# WS2812-Ring.net
KiCad netlist of a schematic drawn in EAGLE
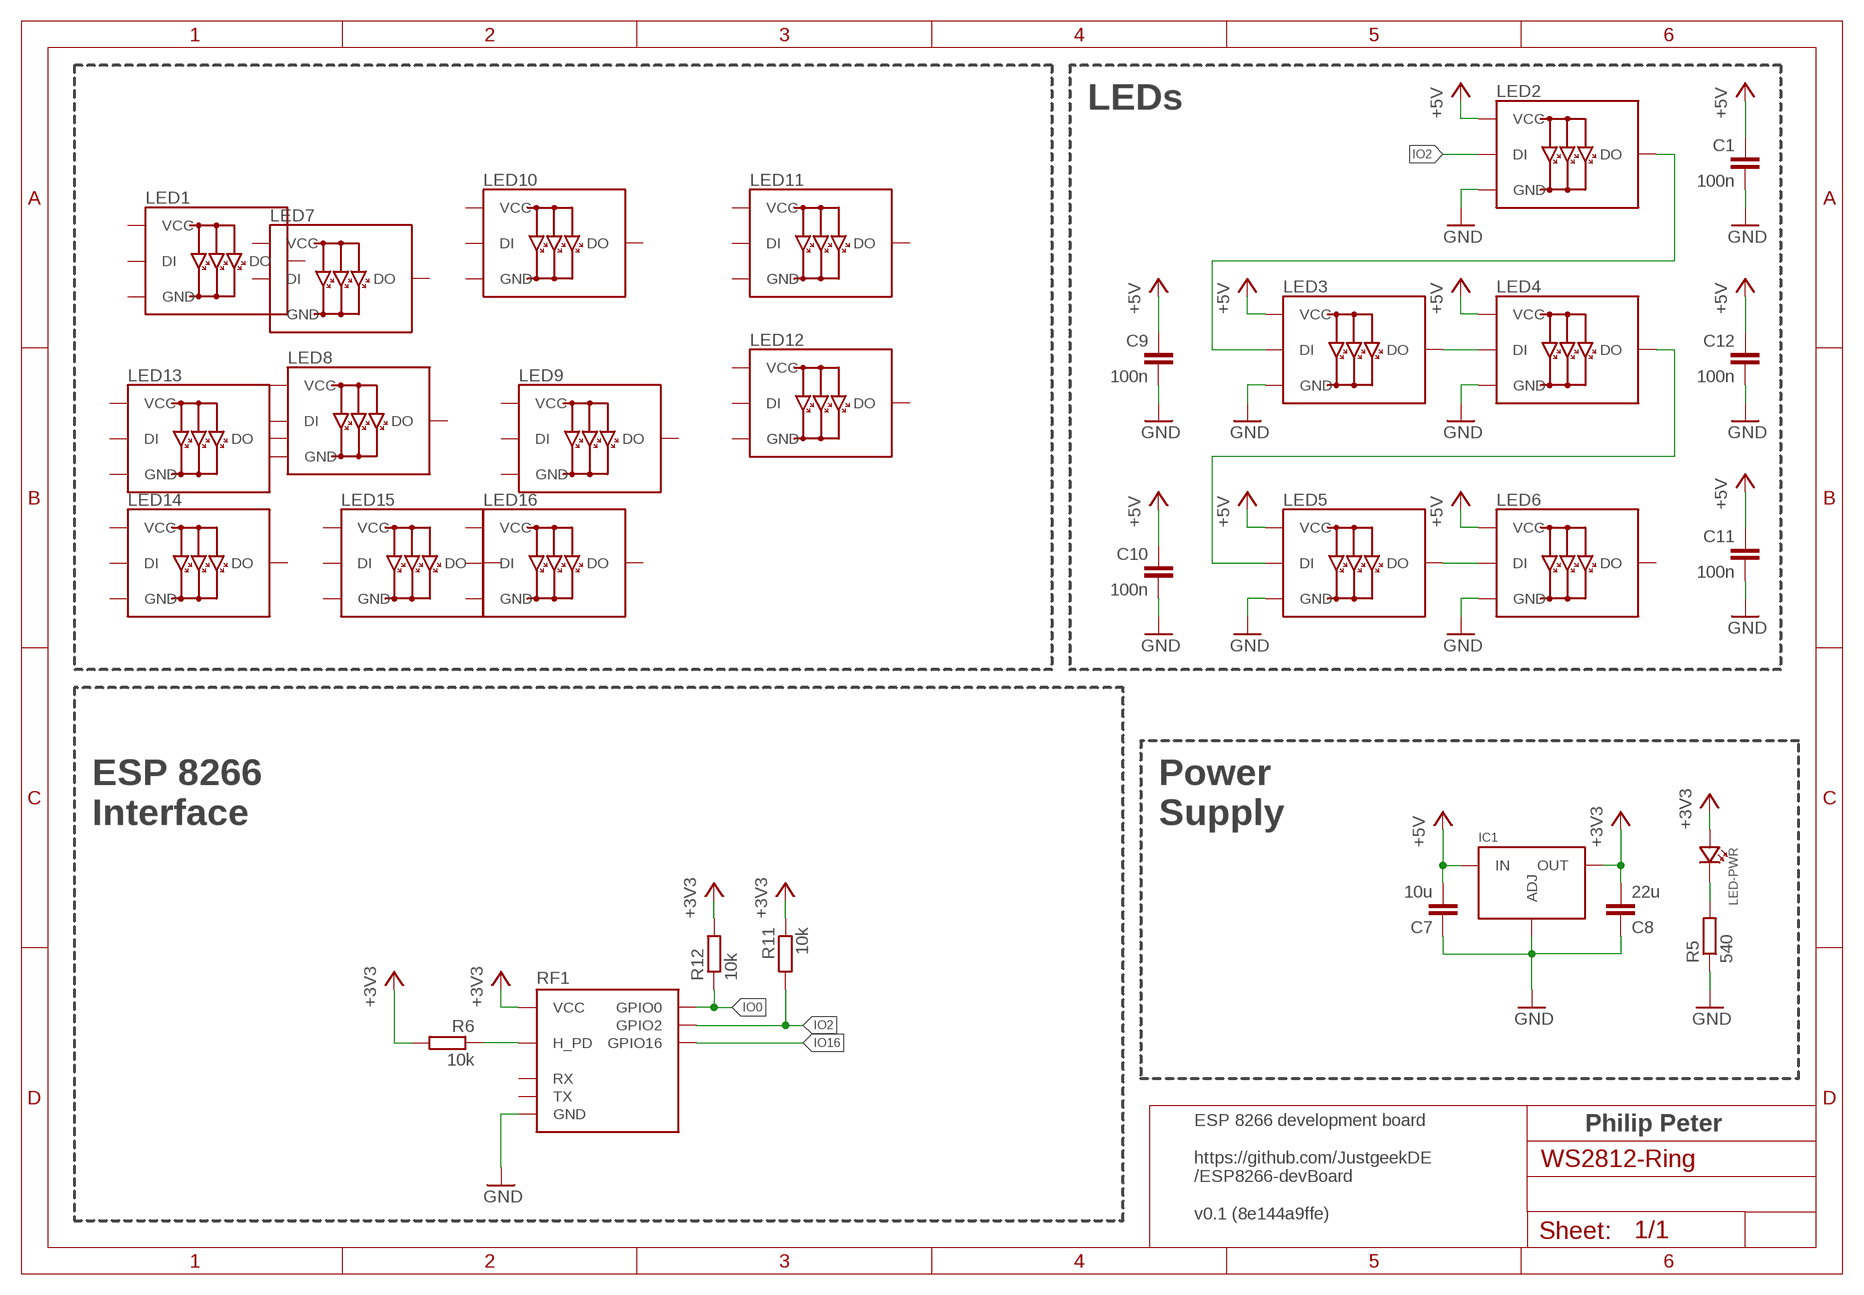
[diagram p0: schematic, sheet 1]

(export (version "E")
  (design (tool "Eeschema 10.0.6"))
  (components
    (comp (ref "C1")
      (value "100n")
      (footprint "eagle-import:C0805")
      (libsource (lib "eagle-import") (part "C-EUC0805"))
    )
    (comp (ref "C7")
      (value "10u")
      (footprint "eagle-import:C0805")
      (libsource (lib "eagle-import") (part "C-EUC0805"))
    )
    (comp (ref "C8")
      (value "22u")
      (footprint "eagle-import:C0805")
      (libsource (lib "eagle-import") (part "C-EUC0805"))
    )
    (comp (ref "C9")
      (value "100n")
      (footprint "eagle-import:C0805")
      (libsource (lib "eagle-import") (part "C-EUC0805"))
    )
    (comp (ref "C10")
      (value "100n")
      (footprint "eagle-import:C0805")
      (libsource (lib "eagle-import") (part "C-EUC0805"))
    )
    (comp (ref "C11")
      (value "100n")
      (footprint "eagle-import:C0805")
      (libsource (lib "eagle-import") (part "C-EUC0805"))
    )
    (comp (ref "C12")
      (value "100n")
      (footprint "eagle-import:C0805")
      (libsource (lib "eagle-import") (part "C-EUC0805"))
    )
    (comp (ref "IC1")
      (value "REGULATOR-LM317-SOT223")
      (footprint "eagle-import:SOT223")
      (libsource (lib "eagle-import") (part "REGULATOR-LM317-SOT223"))
    )
    (comp (ref "LED-PWR")
      (value "LED0805")
      (footprint "eagle-import:CHIPLED_0805")
      (libsource (lib "eagle-import") (part "LED0805"))
    )
    (comp (ref "LED1")
      (value "WS2812B")
      (footprint "eagle-import:CHIP-5050-4_PIN")
      (libsource (lib "eagle-import") (part "WS2812B"))
    )
    (comp (ref "LED2")
      (value "WS2812B")
      (footprint "eagle-import:CHIP-5050-4_PIN")
      (libsource (lib "eagle-import") (part "WS2812B"))
    )
    (comp (ref "LED3")
      (value "WS2812B")
      (footprint "eagle-import:CHIP-5050-4_PIN")
      (libsource (lib "eagle-import") (part "WS2812B"))
    )
    (comp (ref "LED4")
      (value "WS2812B")
      (footprint "eagle-import:CHIP-5050-4_PIN")
      (libsource (lib "eagle-import") (part "WS2812B"))
    )
    (comp (ref "LED5")
      (value "WS2812B")
      (footprint "eagle-import:CHIP-5050-4_PIN")
      (libsource (lib "eagle-import") (part "WS2812B"))
    )
    (comp (ref "LED6")
      (value "WS2812B")
      (footprint "eagle-import:CHIP-5050-4_PIN")
      (libsource (lib "eagle-import") (part "WS2812B"))
    )
    (comp (ref "LED7")
      (value "WS2812B")
      (footprint "eagle-import:CHIP-5050-4_PIN")
      (libsource (lib "eagle-import") (part "WS2812B"))
    )
    (comp (ref "LED8")
      (value "WS2812B")
      (footprint "eagle-import:CHIP-5050-4_PIN")
      (libsource (lib "eagle-import") (part "WS2812B"))
    )
    (comp (ref "LED9")
      (value "WS2812B")
      (footprint "eagle-import:CHIP-5050-4_PIN")
      (libsource (lib "eagle-import") (part "WS2812B"))
    )
    (comp (ref "LED10")
      (value "WS2812B")
      (footprint "eagle-import:CHIP-5050-4_PIN")
      (libsource (lib "eagle-import") (part "WS2812B"))
    )
    (comp (ref "LED11")
      (value "WS2812B")
      (footprint "eagle-import:CHIP-5050-4_PIN")
      (libsource (lib "eagle-import") (part "WS2812B"))
    )
    (comp (ref "LED12")
      (value "WS2812B")
      (footprint "eagle-import:CHIP-5050-4_PIN")
      (libsource (lib "eagle-import") (part "WS2812B"))
    )
    (comp (ref "LED13")
      (value "WS2812B")
      (footprint "eagle-import:CHIP-5050-4_PIN")
      (libsource (lib "eagle-import") (part "WS2812B"))
    )
    (comp (ref "LED14")
      (value "WS2812B")
      (footprint "eagle-import:CHIP-5050-4_PIN")
      (libsource (lib "eagle-import") (part "WS2812B"))
    )
    (comp (ref "LED15")
      (value "WS2812B")
      (footprint "eagle-import:CHIP-5050-4_PIN")
      (libsource (lib "eagle-import") (part "WS2812B"))
    )
    (comp (ref "LED16")
      (value "WS2812B")
      (footprint "eagle-import:CHIP-5050-4_PIN")
      (libsource (lib "eagle-import") (part "WS2812B"))
    )
    (comp (ref "R5")
      (value "540")
      (footprint "eagle-import:R0805")
      (libsource (lib "eagle-import") (part "R-EU_R0805"))
    )
    (comp (ref "R6")
      (value "10k")
      (footprint "eagle-import:R0805")
      (libsource (lib "eagle-import") (part "R-EU_R0805"))
    )
    (comp (ref "R11")
      (value "10k")
      (footprint "eagle-import:R0805")
      (libsource (lib "eagle-import") (part "R-EU_R0805"))
    )
    (comp (ref "R12")
      (value "10k")
      (footprint "eagle-import:R0805")
      (libsource (lib "eagle-import") (part "R-EU_R0805"))
    )
    (comp (ref "RF1")
      (value "ESP2866-ESP-01THT")
      (footprint "eagle-import:ESP8266-ESP-01")
      (libsource (lib "eagle-import") (part "ESP2866-ESP-01THT"))
    )
  )
  (nets
    (net (code "1") (name "+3V3") (class "Default")
      (node (ref "C8") (pin "2") (pinfunction "2_2") (pintype "passive"))
      (node (ref "IC1") (pin "2") (pinfunction "OUT_2") (pintype "bidirectional"))
      (node (ref "IC1") (pin "4") (pinfunction "OUT_4") (pintype "bidirectional"))
      (node (ref "LED-PWR") (pin "A") (pinfunction "A_A") (pintype "bidirectional"))
      (node (ref "R11") (pin "1") (pinfunction "1_1") (pintype "passive"))
      (node (ref "R12") (pin "2") (pinfunction "2_2") (pintype "passive"))
      (node (ref "R6") (pin "2") (pinfunction "2_2") (pintype "passive"))
      (node (ref "RF1") (pin "VCC") (pinfunction "VCC_VCC") (pintype "bidirectional"))
    )
    (net (code "2") (name "+5V") (class "Default")
      (node (ref "C1") (pin "1") (pinfunction "1_1") (pintype "passive"))
      (node (ref "C10") (pin "1") (pinfunction "1_1") (pintype "passive"))
      (node (ref "C11") (pin "1") (pinfunction "1_1") (pintype "passive"))
      (node (ref "C12") (pin "1") (pinfunction "1_1") (pintype "passive"))
      (node (ref "C7") (pin "2") (pinfunction "2_2") (pintype "passive"))
      (node (ref "C9") (pin "1") (pinfunction "1_1") (pintype "passive"))
      (node (ref "IC1") (pin "3") (pinfunction "IN_3") (pintype "bidirectional"))
      (node (ref "LED2") (pin "P$1") (pinfunction "VCC_P$1") (pintype "bidirectional"))
      (node (ref "LED3") (pin "P$1") (pinfunction "VCC_P$1") (pintype "bidirectional"))
      (node (ref "LED4") (pin "P$1") (pinfunction "VCC_P$1") (pintype "bidirectional"))
      (node (ref "LED5") (pin "P$1") (pinfunction "VCC_P$1") (pintype "bidirectional"))
      (node (ref "LED6") (pin "P$1") (pinfunction "VCC_P$1") (pintype "bidirectional"))
    )
    (net (code "3") (name "GND") (class "Default")
      (node (ref "C1") (pin "2") (pinfunction "2_2") (pintype "passive"))
      (node (ref "C10") (pin "2") (pinfunction "2_2") (pintype "passive"))
      (node (ref "C11") (pin "2") (pinfunction "2_2") (pintype "passive"))
      (node (ref "C12") (pin "2") (pinfunction "2_2") (pintype "passive"))
      (node (ref "C7") (pin "1") (pinfunction "1_1") (pintype "passive"))
      (node (ref "C8") (pin "1") (pinfunction "1_1") (pintype "passive"))
      (node (ref "C9") (pin "2") (pinfunction "2_2") (pintype "passive"))
      (node (ref "IC1") (pin "1") (pinfunction "ADJ_1") (pintype "bidirectional"))
      (node (ref "LED2") (pin "P$3") (pinfunction "GND_P$3") (pintype "bidirectional"))
      (node (ref "LED3") (pin "P$3") (pinfunction "GND_P$3") (pintype "bidirectional"))
      (node (ref "LED4") (pin "P$3") (pinfunction "GND_P$3") (pintype "bidirectional"))
      (node (ref "LED5") (pin "P$3") (pinfunction "GND_P$3") (pintype "bidirectional"))
      (node (ref "LED6") (pin "P$3") (pinfunction "GND_P$3") (pintype "bidirectional"))
      (node (ref "R5") (pin "1") (pinfunction "1_1") (pintype "passive"))
      (node (ref "RF1") (pin "GND") (pinfunction "GND_GND") (pintype "bidirectional"))
    )
    (net (code "4") (name "IO0") (class "Default")
      (node (ref "R12") (pin "1") (pinfunction "1_1") (pintype "passive"))
      (node (ref "RF1") (pin "GPIO0") (pinfunction "GPIO0_GPIO0") (pintype "bidirectional"))
    )
    (net (code "5") (name "IO2") (class "Default")
      (node (ref "LED2") (pin "P$4") (pinfunction "DI_P$4") (pintype "bidirectional"))
      (node (ref "R11") (pin "2") (pinfunction "2_2") (pintype "passive"))
      (node (ref "RF1") (pin "GPIO2") (pinfunction "GPIO2_GPIO2") (pintype "bidirectional"))
    )
    (net (code "6") (name "IO16") (class "Default")
      (node (ref "RF1") (pin "GPIO16") (pinfunction "GPIO16_GPIO16") (pintype "bidirectional"))
    )
    (net (code "7") (name "Net-(LED-PWR-PadC)") (class "Default")
      (node (ref "LED-PWR") (pin "C") (pinfunction "C_C") (pintype "bidirectional"))
      (node (ref "R5") (pin "2") (pinfunction "2_2") (pintype "passive"))
    )
    (net (code "8") (name "Net-(LED2-DO)") (class "Default")
      (node (ref "LED2") (pin "P$2") (pinfunction "DO_P$2") (pintype "bidirectional"))
      (node (ref "LED3") (pin "P$4") (pinfunction "DI_P$4") (pintype "bidirectional"))
    )
    (net (code "9") (name "Net-(LED3-DO)") (class "Default")
      (node (ref "LED3") (pin "P$2") (pinfunction "DO_P$2") (pintype "bidirectional"))
      (node (ref "LED4") (pin "P$4") (pinfunction "DI_P$4") (pintype "bidirectional"))
    )
    (net (code "10") (name "Net-(LED4-DO)") (class "Default")
      (node (ref "LED4") (pin "P$2") (pinfunction "DO_P$2") (pintype "bidirectional"))
      (node (ref "LED5") (pin "P$4") (pinfunction "DI_P$4") (pintype "bidirectional"))
    )
    (net (code "11") (name "Net-(LED5-DO)") (class "Default")
      (node (ref "LED5") (pin "P$2") (pinfunction "DO_P$2") (pintype "bidirectional"))
      (node (ref "LED6") (pin "P$4") (pinfunction "DI_P$4") (pintype "bidirectional"))
    )
    (net (code "12") (name "Net-(R6-Pad1)") (class "Default")
      (node (ref "R6") (pin "1") (pinfunction "1_1") (pintype "passive"))
      (node (ref "RF1") (pin "H_PD") (pinfunction "H_PD_H_PD") (pintype "bidirectional"))
    )
    (net (code "13") (name "unconnected-(LED1-DI-PadP$4)") (class "Default")
      (node (ref "LED1") (pin "P$4") (pinfunction "DI_P$4") (pintype "bidirectional"))
    )
    (net (code "14") (name "unconnected-(LED1-DO-PadP$2)") (class "Default")
      (node (ref "LED1") (pin "P$2") (pinfunction "DO_P$2") (pintype "bidirectional"))
    )
    (net (code "15") (name "unconnected-(LED1-GND-PadP$3)") (class "Default")
      (node (ref "LED1") (pin "P$3") (pinfunction "GND_P$3") (pintype "bidirectional"))
    )
    (net (code "16") (name "unconnected-(LED1-VCC-PadP$1)") (class "Default")
      (node (ref "LED1") (pin "P$1") (pinfunction "VCC_P$1") (pintype "bidirectional"))
    )
    (net (code "17") (name "unconnected-(LED6-DO-PadP$2)") (class "Default")
      (node (ref "LED6") (pin "P$2") (pinfunction "DO_P$2") (pintype "bidirectional"))
    )
    (net (code "18") (name "unconnected-(LED7-DI-PadP$4)") (class "Default")
      (node (ref "LED7") (pin "P$4") (pinfunction "DI_P$4") (pintype "bidirectional"))
    )
    (net (code "19") (name "unconnected-(LED7-DO-PadP$2)") (class "Default")
      (node (ref "LED7") (pin "P$2") (pinfunction "DO_P$2") (pintype "bidirectional"))
    )
    (net (code "20") (name "unconnected-(LED7-GND-PadP$3)") (class "Default")
      (node (ref "LED7") (pin "P$3") (pinfunction "GND_P$3") (pintype "bidirectional"))
    )
    (net (code "21") (name "unconnected-(LED7-VCC-PadP$1)") (class "Default")
      (node (ref "LED7") (pin "P$1") (pinfunction "VCC_P$1") (pintype "bidirectional"))
    )
    (net (code "22") (name "unconnected-(LED8-DI-PadP$4)") (class "Default")
      (node (ref "LED8") (pin "P$4") (pinfunction "DI_P$4") (pintype "bidirectional"))
    )
    (net (code "23") (name "unconnected-(LED8-DO-PadP$2)") (class "Default")
      (node (ref "LED8") (pin "P$2") (pinfunction "DO_P$2") (pintype "bidirectional"))
    )
    (net (code "24") (name "unconnected-(LED8-GND-PadP$3)") (class "Default")
      (node (ref "LED8") (pin "P$3") (pinfunction "GND_P$3") (pintype "bidirectional"))
    )
    (net (code "25") (name "unconnected-(LED8-VCC-PadP$1)") (class "Default")
      (node (ref "LED8") (pin "P$1") (pinfunction "VCC_P$1") (pintype "bidirectional"))
    )
    (net (code "26") (name "unconnected-(LED9-DI-PadP$4)") (class "Default")
      (node (ref "LED9") (pin "P$4") (pinfunction "DI_P$4") (pintype "bidirectional"))
    )
    (net (code "27") (name "unconnected-(LED9-DO-PadP$2)") (class "Default")
      (node (ref "LED9") (pin "P$2") (pinfunction "DO_P$2") (pintype "bidirectional"))
    )
    (net (code "28") (name "unconnected-(LED9-GND-PadP$3)") (class "Default")
      (node (ref "LED9") (pin "P$3") (pinfunction "GND_P$3") (pintype "bidirectional"))
    )
    (net (code "29") (name "unconnected-(LED9-VCC-PadP$1)") (class "Default")
      (node (ref "LED9") (pin "P$1") (pinfunction "VCC_P$1") (pintype "bidirectional"))
    )
    (net (code "30") (name "unconnected-(LED10-DI-PadP$4)") (class "Default")
      (node (ref "LED10") (pin "P$4") (pinfunction "DI_P$4") (pintype "bidirectional"))
    )
    (net (code "31") (name "unconnected-(LED10-DO-PadP$2)") (class "Default")
      (node (ref "LED10") (pin "P$2") (pinfunction "DO_P$2") (pintype "bidirectional"))
    )
    (net (code "32") (name "unconnected-(LED10-GND-PadP$3)") (class "Default")
      (node (ref "LED10") (pin "P$3") (pinfunction "GND_P$3") (pintype "bidirectional"))
    )
    (net (code "33") (name "unconnected-(LED10-VCC-PadP$1)") (class "Default")
      (node (ref "LED10") (pin "P$1") (pinfunction "VCC_P$1") (pintype "bidirectional"))
    )
    (net (code "34") (name "unconnected-(LED11-DI-PadP$4)") (class "Default")
      (node (ref "LED11") (pin "P$4") (pinfunction "DI_P$4") (pintype "bidirectional"))
    )
    (net (code "35") (name "unconnected-(LED11-DO-PadP$2)") (class "Default")
      (node (ref "LED11") (pin "P$2") (pinfunction "DO_P$2") (pintype "bidirectional"))
    )
    (net (code "36") (name "unconnected-(LED11-GND-PadP$3)") (class "Default")
      (node (ref "LED11") (pin "P$3") (pinfunction "GND_P$3") (pintype "bidirectional"))
    )
    (net (code "37") (name "unconnected-(LED11-VCC-PadP$1)") (class "Default")
      (node (ref "LED11") (pin "P$1") (pinfunction "VCC_P$1") (pintype "bidirectional"))
    )
    (net (code "38") (name "unconnected-(LED12-DI-PadP$4)") (class "Default")
      (node (ref "LED12") (pin "P$4") (pinfunction "DI_P$4") (pintype "bidirectional"))
    )
    (net (code "39") (name "unconnected-(LED12-DO-PadP$2)") (class "Default")
      (node (ref "LED12") (pin "P$2") (pinfunction "DO_P$2") (pintype "bidirectional"))
    )
    (net (code "40") (name "unconnected-(LED12-GND-PadP$3)") (class "Default")
      (node (ref "LED12") (pin "P$3") (pinfunction "GND_P$3") (pintype "bidirectional"))
    )
    (net (code "41") (name "unconnected-(LED12-VCC-PadP$1)") (class "Default")
      (node (ref "LED12") (pin "P$1") (pinfunction "VCC_P$1") (pintype "bidirectional"))
    )
    (net (code "42") (name "unconnected-(LED13-DI-PadP$4)") (class "Default")
      (node (ref "LED13") (pin "P$4") (pinfunction "DI_P$4") (pintype "bidirectional"))
    )
    (net (code "43") (name "unconnected-(LED13-DO-PadP$2)") (class "Default")
      (node (ref "LED13") (pin "P$2") (pinfunction "DO_P$2") (pintype "bidirectional"))
    )
    (net (code "44") (name "unconnected-(LED13-GND-PadP$3)") (class "Default")
      (node (ref "LED13") (pin "P$3") (pinfunction "GND_P$3") (pintype "bidirectional"))
    )
    (net (code "45") (name "unconnected-(LED13-VCC-PadP$1)") (class "Default")
      (node (ref "LED13") (pin "P$1") (pinfunction "VCC_P$1") (pintype "bidirectional"))
    )
    (net (code "46") (name "unconnected-(LED14-DI-PadP$4)") (class "Default")
      (node (ref "LED14") (pin "P$4") (pinfunction "DI_P$4") (pintype "bidirectional"))
    )
    (net (code "47") (name "unconnected-(LED14-DO-PadP$2)") (class "Default")
      (node (ref "LED14") (pin "P$2") (pinfunction "DO_P$2") (pintype "bidirectional"))
    )
    (net (code "48") (name "unconnected-(LED14-GND-PadP$3)") (class "Default")
      (node (ref "LED14") (pin "P$3") (pinfunction "GND_P$3") (pintype "bidirectional"))
    )
    (net (code "49") (name "unconnected-(LED14-VCC-PadP$1)") (class "Default")
      (node (ref "LED14") (pin "P$1") (pinfunction "VCC_P$1") (pintype "bidirectional"))
    )
    (net (code "50") (name "unconnected-(LED15-DI-PadP$4)") (class "Default")
      (node (ref "LED15") (pin "P$4") (pinfunction "DI_P$4") (pintype "bidirectional"))
    )
    (net (code "51") (name "unconnected-(LED15-DO-PadP$2)") (class "Default")
      (node (ref "LED15") (pin "P$2") (pinfunction "DO_P$2") (pintype "bidirectional"))
    )
    (net (code "52") (name "unconnected-(LED15-GND-PadP$3)") (class "Default")
      (node (ref "LED15") (pin "P$3") (pinfunction "GND_P$3") (pintype "bidirectional"))
    )
    (net (code "53") (name "unconnected-(LED15-VCC-PadP$1)") (class "Default")
      (node (ref "LED15") (pin "P$1") (pinfunction "VCC_P$1") (pintype "bidirectional"))
    )
    (net (code "54") (name "unconnected-(LED16-DI-PadP$4)") (class "Default")
      (node (ref "LED16") (pin "P$4") (pinfunction "DI_P$4") (pintype "bidirectional"))
    )
    (net (code "55") (name "unconnected-(LED16-DO-PadP$2)") (class "Default")
      (node (ref "LED16") (pin "P$2") (pinfunction "DO_P$2") (pintype "bidirectional"))
    )
    (net (code "56") (name "unconnected-(LED16-GND-PadP$3)") (class "Default")
      (node (ref "LED16") (pin "P$3") (pinfunction "GND_P$3") (pintype "bidirectional"))
    )
    (net (code "57") (name "unconnected-(LED16-VCC-PadP$1)") (class "Default")
      (node (ref "LED16") (pin "P$1") (pinfunction "VCC_P$1") (pintype "bidirectional"))
    )
    (net (code "58") (name "unconnected-(RF1-PadRX)") (class "Default")
      (node (ref "RF1") (pin "RX") (pinfunction "RX_RX") (pintype "bidirectional"))
    )
    (net (code "59") (name "unconnected-(RF1-PadTX)") (class "Default")
      (node (ref "RF1") (pin "TX") (pinfunction "TX_TX") (pintype "bidirectional"))
    )
  )
)
